# broken_spiritlevel_top.net
KiCad netlist of a schematic drawn in Altium Designer
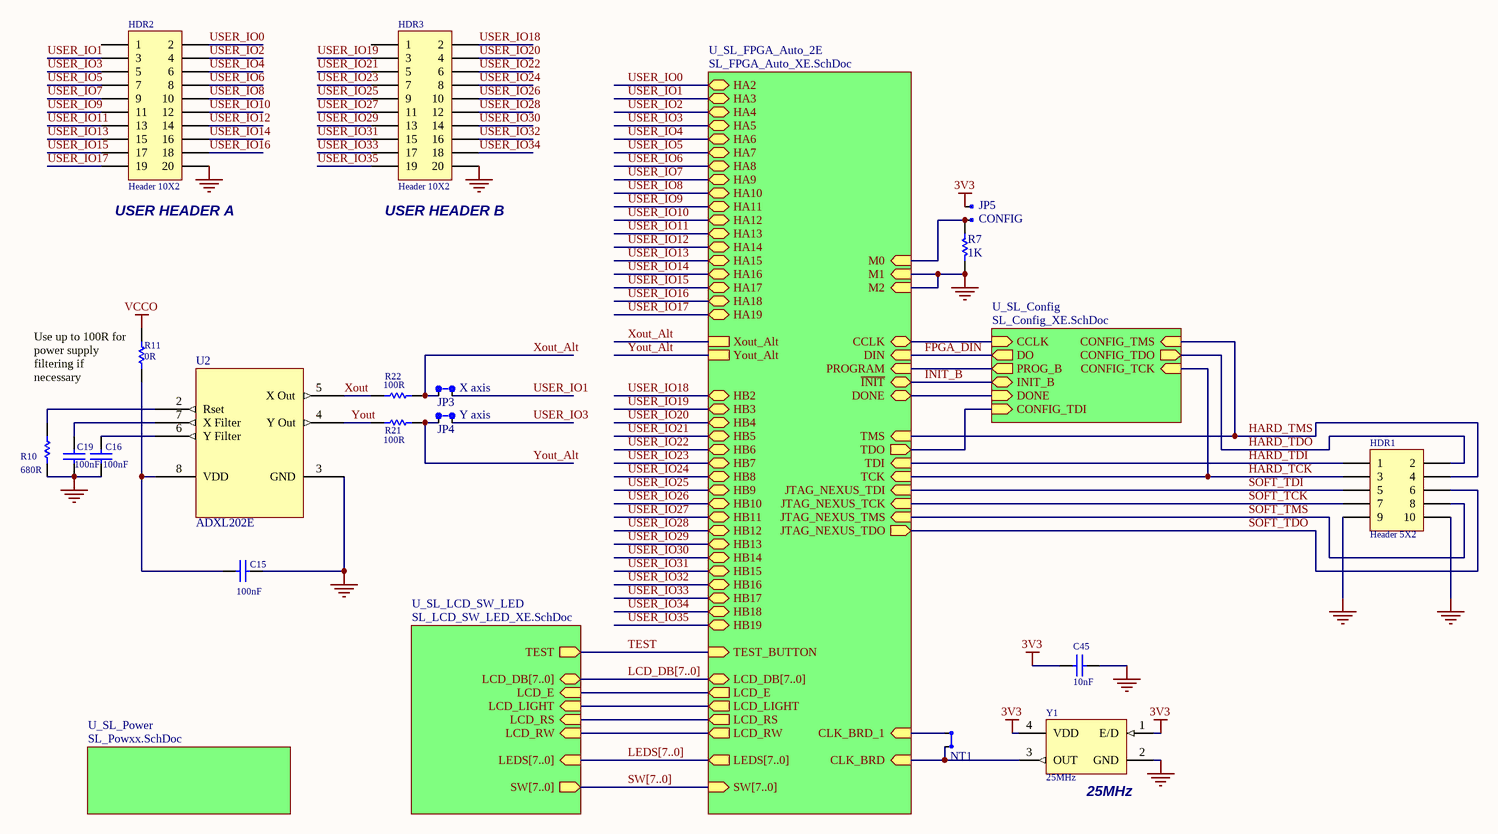
[diagram p0: broken_spiritlevel_top.SchDoc]

(export (version "E")
  (design (tool "Eeschema 10.0.6"))
  (components
    (comp (ref "C15")
      (value "100nF")
      (footprint "CC1608-0603")
      (description "Capacitor")
      (libsource (lib "SpiritLevel_2E") (part "CAP"))
    )
    (comp (ref "C16")
      (value "100nF")
      (footprint "CC1608-0603")
      (description "Capacitor")
      (libsource (lib "SpiritLevel_2E") (part "CAP"))
    )
    (comp (ref "C19")
      (value "100nF")
      (footprint "CC1608-0603")
      (description "Capacitor")
      (libsource (lib "SpiritLevel_2E") (part "CAP"))
    )
    (comp (ref "C45")
      (value "10nF")
      (footprint "CC1608-0603")
      (description "Capacitor")
      (libsource (lib "SpiritLevel_2E") (part "CAP"))
    )
    (comp (ref "HDR1")
      (value "Header 5X2")
      (footprint "Spirit_Level_Project:HDR2X5_LP")
      (description "Header, 5-Pin, Dual row")
      (libsource (lib "SpiritLevel_2E") (part "Header 5X2"))
    )
    (comp (ref "HDR2")
      (value "Header 10X2")
      (footprint "Spirit_Level_Project:HDR2X10")
      (description "Header, 10-Pin, Dual row")
      (libsource (lib "SpiritLevel_2E") (part "Header 10X2"))
    )
    (comp (ref "HDR3")
      (value "Header 10X2")
      (footprint "Spirit_Level_Project:HDR2X10")
      (description "Header, 10-Pin, Dual row")
      (libsource (lib "SpiritLevel_2E") (part "Header 10X2"))
    )
    (comp (ref "JP3")
      (value "X axis")
      (footprint "Spirit_Level_Project:HDR1X2")
      (description "Jumper, 2-Pin")
      (libsource (lib "SpiritLevel_2E") (part "Jumper, 2-Pin"))
    )
    (comp (ref "JP4")
      (value "Y axis")
      (footprint "Spirit_Level_Project:HDR1X2")
      (description "Jumper, 2-Pin")
      (libsource (lib "SpiritLevel_2E") (part "Jumper, 2-Pin"))
    )
    (comp (ref "JP5")
      (value "CONFIG")
      (footprint "Spirit_Level_Project:HDR1X2")
      (description "Jumper, 2-Pin")
      (libsource (lib "SpiritLevel_2E") (part "Jumper, 2-Pin"))
    )
    (comp (ref "JS2")
      (value "Short Linking")
      (description "Shorting Link, 2.54mm (0.1\") Pitch")
      (libsource (lib "SpiritLevel_2E") (part "Jumper Socket"))
    )
    (comp (ref "JS3")
      (value "Shorting Link")
      (description "Shorting Link, 2.54mm (0.1\") Pitch")
      (libsource (lib "SpiritLevel_2E") (part "Jumper Socket"))
    )
    (comp (ref "NT1")
      (value "GND")
      (footprint "Spirit_Level_Project:NT")
      (description "Jumper, 2-Pin")
      (libsource (lib "SpiritLevel_2E") (part "Jumper, 2-Pin_1"))
    )
    (comp (ref "R7")
      (value "1K")
      (footprint "Spirit_Level_Project:CR2012-0805")
      (description "Resistor")
      (libsource (lib "SpiritLevel_2E") (part "RES"))
    )
    (comp (ref "R10")
      (value "680R")
      (footprint "Spirit_Level_Project:CR2012-0805")
      (description "Resistor")
      (libsource (lib "SpiritLevel_2E") (part "Res1"))
    )
    (comp (ref "R11")
      (value "0R")
      (footprint "Spirit_Level_Project:CR2012-0805")
      (description "Resistor")
      (libsource (lib "SpiritLevel_2E") (part "RES"))
    )
    (comp (ref "R21")
      (value "100R")
      (footprint "Spirit_Level_Project:CR2012-0805")
      (description "Resistor")
      (libsource (lib "SpiritLevel_2E") (part "Res1"))
    )
    (comp (ref "R22")
      (value "100R")
      (footprint "Spirit_Level_Project:CR2012-0805")
      (description "Resistor")
      (libsource (lib "SpiritLevel_2E") (part "Res1"))
    )
    (comp (ref "U2")
      (value "ADXL202E")
      (footprint "Spirit_Level_Project:E-8")
      (description "Accelerometer with Digital Output")
      (libsource (lib "SpiritLevel_2E") (part "ADXL202E"))
    )
    (comp (ref "Y1")
      (value "25MHz")
      (footprint "Spirit_Level_Project:QSMO_4200")
      (description "Surface Mount Crystal Oscillator")
      (libsource (lib "SpiritLevel_2E") (part "QSMO_4200"))
    )
  )
  (nets
    (net (code "26") (name "/CLK_BRD") (class "Default")
      (node (ref "NT1") (pin "2") (pinfunction "2_2") (pintype "passive"))
      (node (ref "Y1") (pin "3") (pinfunction "OUT_3") (pintype "output"))
    )
    (net (code "27") (name "/CLK_BRD_1") (class "Default")
      (node (ref "NT1") (pin "1") (pinfunction "1_1") (pintype "passive"))
    )
    (net (code "30") (name "/HARD_TCK") (class "Default")
      (node (ref "HDR1") (pin "3") (pinfunction "3_3") (pintype "passive"))
    )
    (net (code "31") (name "/HARD_TDI") (class "Default")
      (node (ref "HDR1") (pin "1") (pinfunction "1_1") (pintype "passive"))
    )
    (net (code "32") (name "/HARD_TDO") (class "Default")
      (node (ref "HDR1") (pin "2") (pinfunction "2_2") (pintype "passive"))
    )
    (net (code "33") (name "/HARD_TMS") (class "Default")
      (node (ref "HDR1") (pin "4") (pinfunction "4_4") (pintype "passive"))
    )
    (net (code "41") (name "/M0") (class "Default")
      (node (ref "JP5") (pin "1") (pinfunction "1_1") (pintype "passive"))
      (node (ref "R7") (pin "2") (pinfunction "2_2") (pintype "passive"))
    )
    (net (code "43") (name "/SOFT_TCK") (class "Default")
      (node (ref "HDR1") (pin "7") (pinfunction "7_7") (pintype "passive"))
    )
    (net (code "44") (name "/SOFT_TDI") (class "Default")
      (node (ref "HDR1") (pin "5") (pinfunction "5_5") (pintype "passive"))
    )
    (net (code "45") (name "/SOFT_TDO") (class "Default")
      (node (ref "HDR1") (pin "6") (pinfunction "6_6") (pintype "passive"))
    )
    (net (code "46") (name "/SOFT_TMS") (class "Default")
      (node (ref "HDR1") (pin "8") (pinfunction "8_8") (pintype "passive"))
    )
    (net (code "50") (name "/USER_IO0") (class "Default")
      (node (ref "HDR2") (pin "2") (pinfunction "2_2") (pintype "passive"))
    )
    (net (code "51") (name "/USER_IO1") (class "Default")
      (node (ref "HDR2") (pin "3") (pinfunction "3_3") (pintype "passive"))
      (node (ref "JP3") (pin "2") (pinfunction "2_2") (pintype "passive"))
    )
    (net (code "52") (name "/USER_IO2") (class "Default")
      (node (ref "HDR2") (pin "4") (pinfunction "4_4") (pintype "passive"))
    )
    (net (code "53") (name "/USER_IO3") (class "Default")
      (node (ref "HDR2") (pin "5") (pinfunction "5_5") (pintype "passive"))
      (node (ref "JP4") (pin "2") (pinfunction "2_2") (pintype "passive"))
    )
    (net (code "54") (name "/USER_IO4") (class "Default")
      (node (ref "HDR2") (pin "6") (pinfunction "6_6") (pintype "passive"))
    )
    (net (code "55") (name "/USER_IO5") (class "Default")
      (node (ref "HDR2") (pin "7") (pinfunction "7_7") (pintype "passive"))
    )
    (net (code "56") (name "/USER_IO6") (class "Default")
      (node (ref "HDR2") (pin "8") (pinfunction "8_8") (pintype "passive"))
    )
    (net (code "57") (name "/USER_IO7") (class "Default")
      (node (ref "HDR2") (pin "9") (pinfunction "9_9") (pintype "passive"))
    )
    (net (code "58") (name "/USER_IO8") (class "Default")
      (node (ref "HDR2") (pin "10") (pinfunction "10_10") (pintype "passive"))
    )
    (net (code "59") (name "/USER_IO9") (class "Default")
      (node (ref "HDR2") (pin "11") (pinfunction "11_11") (pintype "passive"))
    )
    (net (code "60") (name "/USER_IO10") (class "Default")
      (node (ref "HDR2") (pin "12") (pinfunction "12_12") (pintype "passive"))
    )
    (net (code "61") (name "/USER_IO11") (class "Default")
      (node (ref "HDR2") (pin "13") (pinfunction "13_13") (pintype "passive"))
    )
    (net (code "62") (name "/USER_IO12") (class "Default")
      (node (ref "HDR2") (pin "14") (pinfunction "14_14") (pintype "passive"))
    )
    (net (code "63") (name "/USER_IO13") (class "Default")
      (node (ref "HDR2") (pin "15") (pinfunction "15_15") (pintype "passive"))
    )
    (net (code "64") (name "/USER_IO14") (class "Default")
      (node (ref "HDR2") (pin "16") (pinfunction "16_16") (pintype "passive"))
    )
    (net (code "65") (name "/USER_IO15") (class "Default")
      (node (ref "HDR2") (pin "17") (pinfunction "17_17") (pintype "passive"))
    )
    (net (code "66") (name "/USER_IO16") (class "Default")
      (node (ref "HDR2") (pin "18") (pinfunction "18_18") (pintype "passive"))
    )
    (net (code "67") (name "/USER_IO17") (class "Default")
      (node (ref "HDR2") (pin "19") (pinfunction "19_19") (pintype "passive"))
    )
    (net (code "68") (name "/USER_IO18") (class "Default")
      (node (ref "HDR3") (pin "2") (pinfunction "2_2") (pintype "passive"))
    )
    (net (code "69") (name "/USER_IO19") (class "Default")
      (node (ref "HDR3") (pin "3") (pinfunction "3_3") (pintype "passive"))
    )
    (net (code "70") (name "/USER_IO20") (class "Default")
      (node (ref "HDR3") (pin "4") (pinfunction "4_4") (pintype "passive"))
    )
    (net (code "71") (name "/USER_IO21") (class "Default")
      (node (ref "HDR3") (pin "5") (pinfunction "5_5") (pintype "passive"))
    )
    (net (code "72") (name "/USER_IO22") (class "Default")
      (node (ref "HDR3") (pin "6") (pinfunction "6_6") (pintype "passive"))
    )
    (net (code "73") (name "/USER_IO23") (class "Default")
      (node (ref "HDR3") (pin "7") (pinfunction "7_7") (pintype "passive"))
    )
    (net (code "74") (name "/USER_IO24") (class "Default")
      (node (ref "HDR3") (pin "8") (pinfunction "8_8") (pintype "passive"))
    )
    (net (code "75") (name "/USER_IO25") (class "Default")
      (node (ref "HDR3") (pin "9") (pinfunction "9_9") (pintype "passive"))
    )
    (net (code "76") (name "/USER_IO26") (class "Default")
      (node (ref "HDR3") (pin "10") (pinfunction "10_10") (pintype "passive"))
    )
    (net (code "77") (name "/USER_IO27") (class "Default")
      (node (ref "HDR3") (pin "11") (pinfunction "11_11") (pintype "passive"))
    )
    (net (code "78") (name "/USER_IO28") (class "Default")
      (node (ref "HDR3") (pin "12") (pinfunction "12_12") (pintype "passive"))
    )
    (net (code "79") (name "/USER_IO29") (class "Default")
      (node (ref "HDR3") (pin "13") (pinfunction "13_13") (pintype "passive"))
    )
    (net (code "80") (name "/USER_IO30") (class "Default")
      (node (ref "HDR3") (pin "14") (pinfunction "14_14") (pintype "passive"))
    )
    (net (code "81") (name "/USER_IO31") (class "Default")
      (node (ref "HDR3") (pin "15") (pinfunction "15_15") (pintype "passive"))
    )
    (net (code "82") (name "/USER_IO32") (class "Default")
      (node (ref "HDR3") (pin "16") (pinfunction "16_16") (pintype "passive"))
    )
    (net (code "83") (name "/USER_IO33") (class "Default")
      (node (ref "HDR3") (pin "17") (pinfunction "17_17") (pintype "passive"))
    )
    (net (code "84") (name "/USER_IO34") (class "Default")
      (node (ref "HDR3") (pin "18") (pinfunction "18_18") (pintype "passive"))
    )
    (net (code "85") (name "/USER_IO35") (class "Default")
      (node (ref "HDR3") (pin "19") (pinfunction "19_19") (pintype "passive"))
    )
    (net (code "86") (name "/Xout") (class "Default")
      (node (ref "R22") (pin "2") (pinfunction "2_2") (pintype "passive"))
      (node (ref "U2") (pin "5") (pinfunction "X_Out_5") (pintype "output"))
    )
    (net (code "87") (name "/Xout_Alt") (class "Default")
      (node (ref "JP3") (pin "1") (pinfunction "1_1") (pintype "passive"))
      (node (ref "R22") (pin "1") (pinfunction "1_1") (pintype "passive"))
    )
    (net (code "88") (name "/Yout") (class "Default")
      (node (ref "R21") (pin "2") (pinfunction "2_2") (pintype "passive"))
      (node (ref "U2") (pin "4") (pinfunction "Y_Out_4") (pintype "output"))
    )
    (net (code "89") (name "/Yout_Alt") (class "Default")
      (node (ref "JP4") (pin "1") (pinfunction "1_1") (pintype "passive"))
      (node (ref "R21") (pin "1") (pinfunction "1_1") (pintype "passive"))
    )
    (net (code "90") (name "3V3") (class "Default")
      (node (ref "C45") (pin "1") (pinfunction "1_1") (pintype "passive"))
      (node (ref "JP5") (pin "2") (pinfunction "2_2") (pintype "passive"))
      (node (ref "Y1") (pin "1") (pinfunction "E/D_1") (pintype "input"))
      (node (ref "Y1") (pin "4") (pinfunction "VDD_4") (pintype "power_in"))
    )
    (net (code "91") (name "GND") (class "Default")
      (node (ref "C15") (pin "2") (pinfunction "2_2") (pintype "passive"))
      (node (ref "C16") (pin "2") (pinfunction "2_2") (pintype "passive"))
      (node (ref "C19") (pin "2") (pinfunction "2_2") (pintype "passive"))
      (node (ref "C45") (pin "2") (pinfunction "2_2") (pintype "passive"))
      (node (ref "HDR1") (pin "10") (pinfunction "10_10") (pintype "passive"))
      (node (ref "HDR1") (pin "9") (pinfunction "9_9") (pintype "passive"))
      (node (ref "HDR2") (pin "20") (pinfunction "20_20") (pintype "passive"))
      (node (ref "HDR3") (pin "20") (pinfunction "20_20") (pintype "passive"))
      (node (ref "R10") (pin "1") (pinfunction "1_1") (pintype "passive"))
      (node (ref "R7") (pin "1") (pinfunction "1_1") (pintype "passive"))
      (node (ref "U2") (pin "3") (pinfunction "GND_3") (pintype "power_in"))
      (node (ref "Y1") (pin "2") (pinfunction "GND_2") (pintype "power_in"))
    )
    (net (code "92") (name "Net-(U2-Rset)") (class "Default")
      (node (ref "R10") (pin "2") (pinfunction "2_2") (pintype "passive"))
      (node (ref "U2") (pin "2") (pinfunction "Rset_2") (pintype "output"))
    )
    (net (code "93") (name "Net-(U2-VDD)") (class "Default")
      (node (ref "C15") (pin "1") (pinfunction "1_1") (pintype "passive"))
      (node (ref "R11") (pin "2") (pinfunction "2_2") (pintype "passive"))
      (node (ref "U2") (pin "8") (pinfunction "VDD_8") (pintype "power_in"))
    )
    (net (code "94") (name "Net-(U2-X_Filter)") (class "Default")
      (node (ref "C19") (pin "1") (pinfunction "1_1") (pintype "passive"))
      (node (ref "U2") (pin "7") (pinfunction "X_Filter_7") (pintype "output"))
    )
    (net (code "95") (name "Net-(U2-Y_Filter)") (class "Default")
      (node (ref "C16") (pin "1") (pinfunction "1_1") (pintype "passive"))
      (node (ref "U2") (pin "6") (pinfunction "Y_Filter_6") (pintype "output"))
    )
    (net (code "96") (name "VCCO") (class "Default")
      (node (ref "R11") (pin "1") (pinfunction "1_1") (pintype "passive"))
    )
    (net (code "97") (name "unconnected-(HDR2-Pad1)") (class "Default")
      (node (ref "HDR2") (pin "1") (pinfunction "1_1") (pintype "passive"))
    )
    (net (code "98") (name "unconnected-(HDR3-Pad1)") (class "Default")
      (node (ref "HDR3") (pin "1") (pinfunction "1_1") (pintype "passive"))
    )
    (net (code "99") (name "unconnected-(U2-Self_Test-Pad1)") (class "Default")
      (node (ref "U2") (pin "1") (pinfunction "Self_Test_1") (pintype "input"))
    )
  )
)
